# ESC_and_CYTRON_power.net
KiCad netlist of a schematic drawn in EAGLE
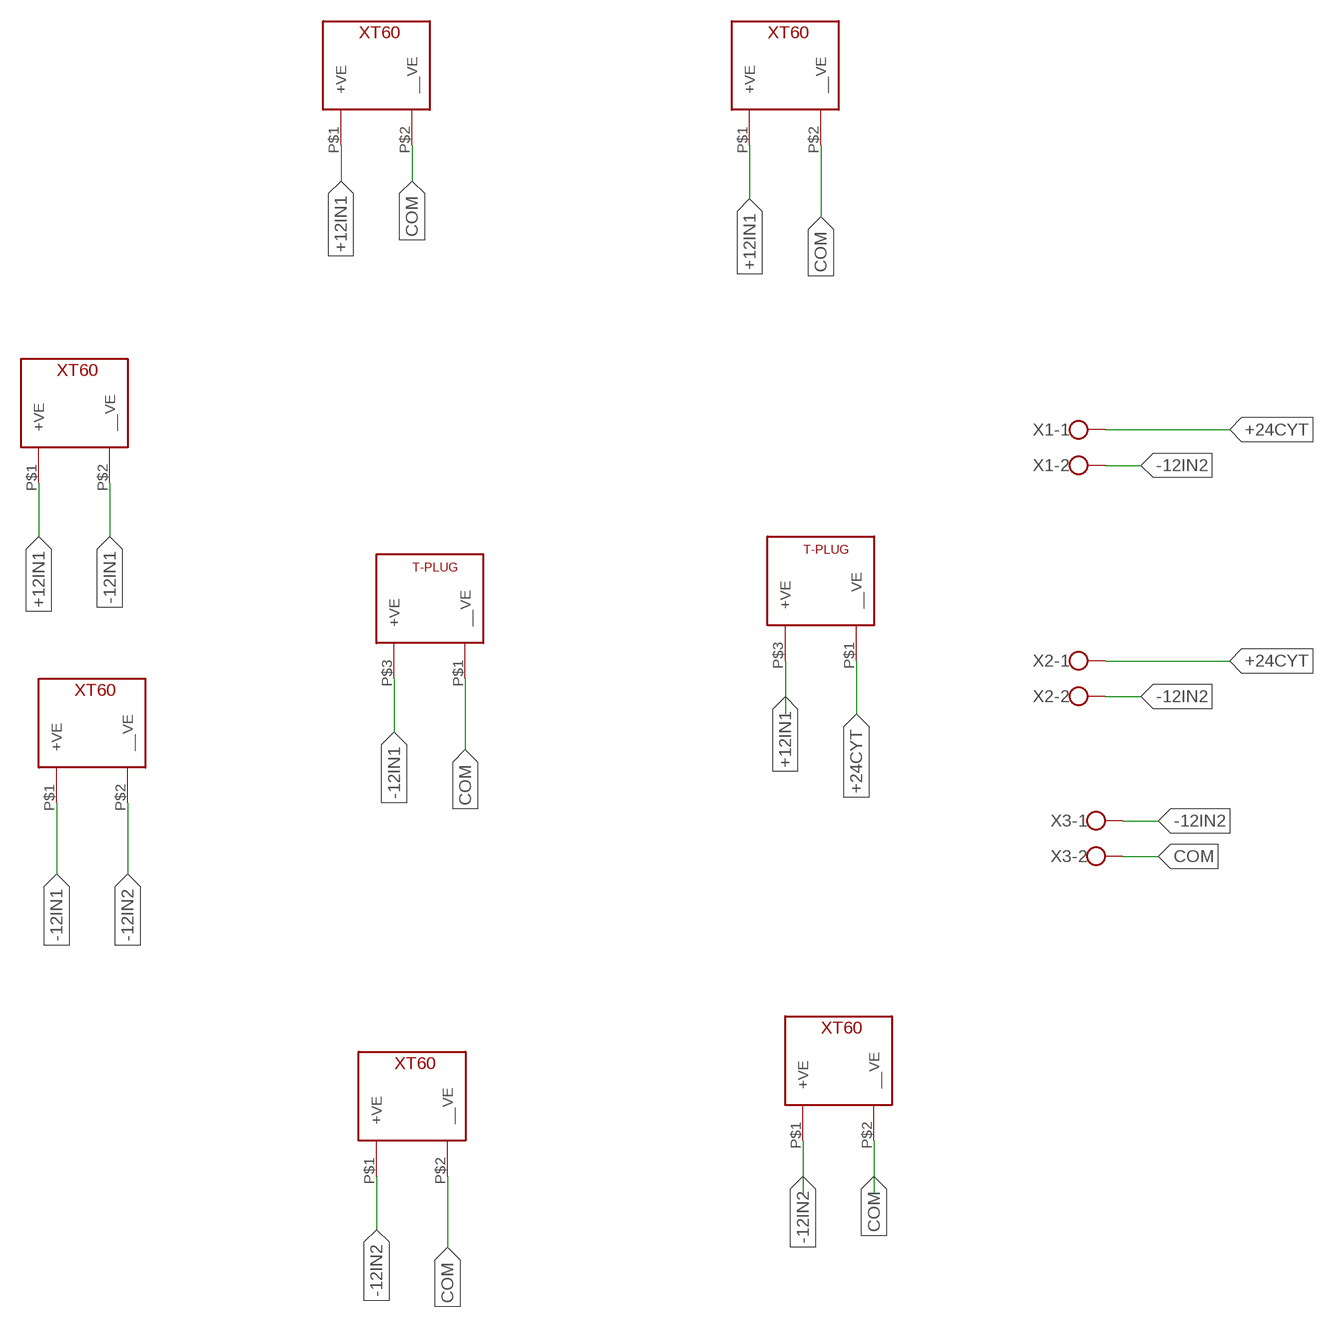
[diagram p0: schematic, sheet 1]

(export (version "E")
  (design (tool "Eeschema 10.0.6"))
  (components
    (comp (ref "BAT1")
      (value "XT60_CONNECTOR")
      (footprint "eagle-import:XT60")
      (libsource (lib "eagle-import") (part "XT60_CONNECTOR"))
    )
    (comp (ref "BAT2")
      (value "XT60_CONNECTOR")
      (footprint "eagle-import:XT60")
      (libsource (lib "eagle-import") (part "XT60_CONNECTOR"))
    )
    (comp (ref "CYT-SW")
      (value "T_CONNECTOR")
      (footprint "eagle-import:T-PLUG")
      (libsource (lib "eagle-import") (part "T_CONNECTOR"))
    )
    (comp (ref "ESC-B1")
      (value "XT60_CONNECTOR")
      (footprint "eagle-import:XT60")
      (libsource (lib "eagle-import") (part "XT60_CONNECTOR"))
    )
    (comp (ref "ESC-B2")
      (value "XT60_CONNECTOR")
      (footprint "eagle-import:XT60")
      (libsource (lib "eagle-import") (part "XT60_CONNECTOR"))
    )
    (comp (ref "ESC-SW")
      (value "T_CONNECTOR")
      (footprint "eagle-import:T-PLUG")
      (libsource (lib "eagle-import") (part "T_CONNECTOR"))
    )
    (comp (ref "ESC-T1")
      (value "XT60_CONNECTOR")
      (footprint "eagle-import:XT60")
      (libsource (lib "eagle-import") (part "XT60_CONNECTOR"))
    )
    (comp (ref "ESC-T2")
      (value "XT60_CONNECTOR")
      (footprint "eagle-import:XT60")
      (libsource (lib "eagle-import") (part "XT60_CONNECTOR"))
    )
    (comp (ref "X1")
      (value "ROSTA.POWER")
      (footprint "eagle-import:W239-302")
      (libsource (lib "eagle-import") (part "ROSTA.POWER"))
    )
    (comp (ref "X2")
      (value "ROSTA.POWER")
      (footprint "eagle-import:W239-302")
      (libsource (lib "eagle-import") (part "ROSTA.POWER"))
    )
    (comp (ref "X3")
      (value "ROSTA.POWER")
      (footprint "eagle-import:W239-302")
      (libsource (lib "eagle-import") (part "ROSTA.POWER"))
    )
  )
  (nets
    (net (code "1") (name "+12IN1") (class "Default")
      (node (ref "BAT1") (pin "P$1") (pinfunction "+VE_P$1") (pintype "bidirectional"))
      (node (ref "CYT-SW") (pin "P$3") (pinfunction "+VE_P$3") (pintype "bidirectional"))
      (node (ref "ESC-T1") (pin "P$1") (pinfunction "+VE_P$1") (pintype "bidirectional"))
      (node (ref "ESC-T2") (pin "P$1") (pinfunction "+VE_P$1") (pintype "bidirectional"))
    )
    (net (code "2") (name "+24CYT") (class "Default")
      (node (ref "CYT-SW") (pin "P$1") (pinfunction "__VE_P$1") (pintype "bidirectional"))
      (node (ref "X1") (pin "1") (pinfunction "KL_1") (pintype "passive"))
      (node (ref "X2") (pin "1") (pinfunction "KL_1") (pintype "passive"))
    )
    (net (code "3") (name "-12IN1") (class "Default")
      (node (ref "BAT1") (pin "P$2") (pinfunction "__VE_P$2") (pintype "bidirectional"))
      (node (ref "BAT2") (pin "P$1") (pinfunction "+VE_P$1") (pintype "bidirectional"))
      (node (ref "ESC-SW") (pin "P$3") (pinfunction "+VE_P$3") (pintype "bidirectional"))
    )
    (net (code "4") (name "-12IN2") (class "Default")
      (node (ref "BAT2") (pin "P$2") (pinfunction "__VE_P$2") (pintype "bidirectional"))
      (node (ref "ESC-B1") (pin "P$1") (pinfunction "+VE_P$1") (pintype "bidirectional"))
      (node (ref "ESC-B2") (pin "P$1") (pinfunction "+VE_P$1") (pintype "bidirectional"))
      (node (ref "X1") (pin "2") (pinfunction "KL_2") (pintype "passive"))
      (node (ref "X2") (pin "2") (pinfunction "KL_2") (pintype "passive"))
      (node (ref "X3") (pin "1") (pinfunction "KL_1") (pintype "passive"))
    )
    (net (code "5") (name "COM") (class "Default")
      (node (ref "ESC-B1") (pin "P$2") (pinfunction "__VE_P$2") (pintype "bidirectional"))
      (node (ref "ESC-B2") (pin "P$2") (pinfunction "__VE_P$2") (pintype "bidirectional"))
      (node (ref "ESC-SW") (pin "P$1") (pinfunction "__VE_P$1") (pintype "bidirectional"))
      (node (ref "ESC-T1") (pin "P$2") (pinfunction "__VE_P$2") (pintype "bidirectional"))
      (node (ref "ESC-T2") (pin "P$2") (pinfunction "__VE_P$2") (pintype "bidirectional"))
      (node (ref "X3") (pin "2") (pinfunction "KL_2") (pintype "passive"))
    )
  )
)
